# LPC1114_--_Valdez_Mutant_v_02.net
KiCad netlist of a schematic drawn in EAGLE
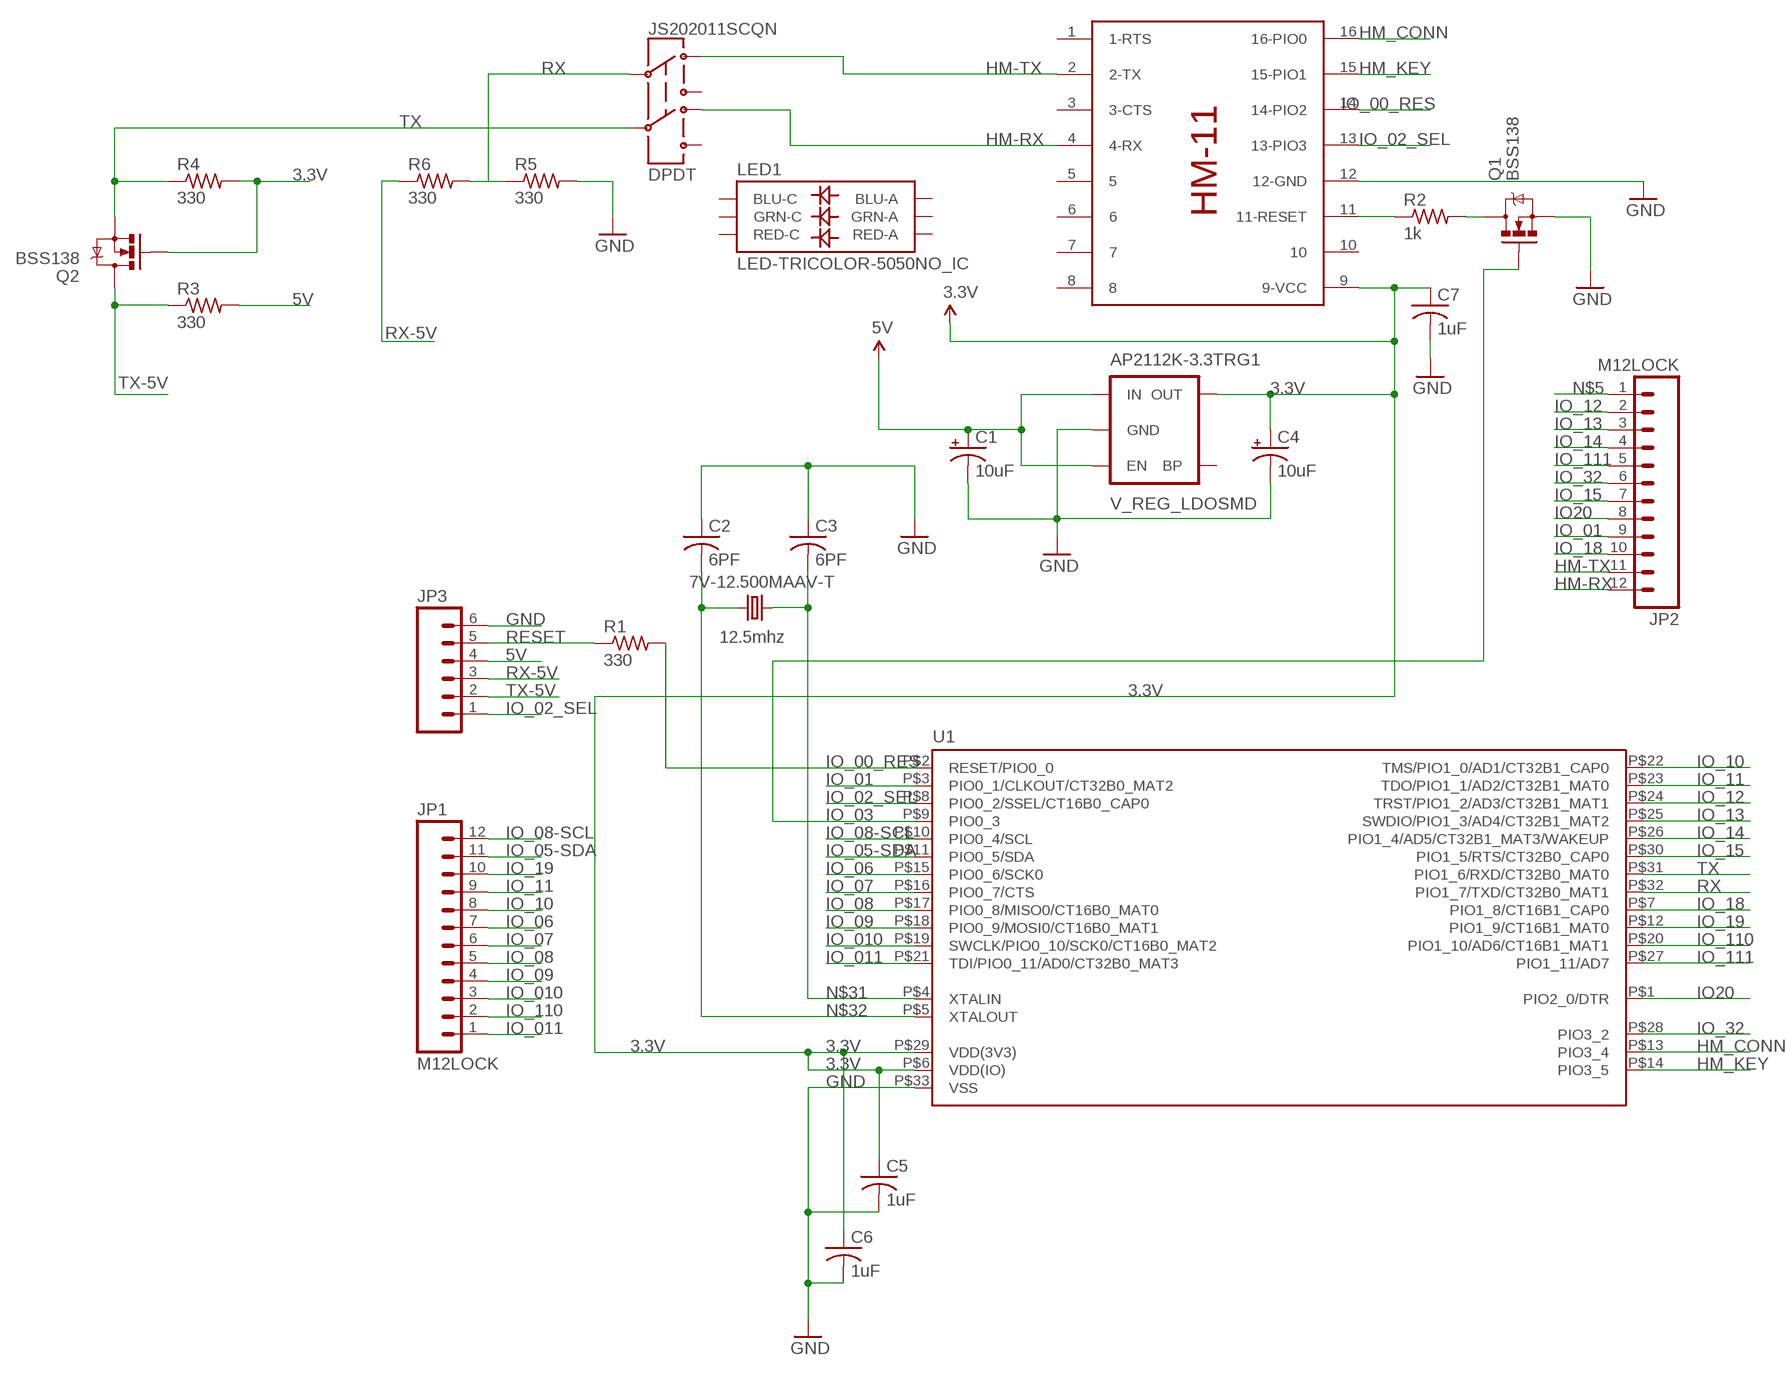
[diagram p0: schematic, sheet 1]

(export (version "E")
  (design (tool "Eeschema 10.0.6"))
  (components
    (comp (ref "7V-12.500MAAV-T")
      (value "12.5mhz")
      (footprint "eagle-import:CRYSTAL-SMD-5X3")
      (libsource (lib "eagle-import") (part "CRYSTAL5X3"))
    )
    (comp (ref "AP2112K-3.3TRG1")
      (value "V_REG_LDOSMD")
      (footprint "eagle-import:SOT23-5")
      (libsource (lib "eagle-import") (part "V_REG_LDOSMD"))
    )
    (comp (ref "C1")
      (value "10uF")
      (footprint "eagle-import:EIA3216")
      (libsource (lib "eagle-import") (part "CAP_POL1206"))
    )
    (comp (ref "C2")
      (value "6PF")
      (footprint "eagle-import:C0402K")
      (libsource (lib "eagle-import") (part "C-USC0402K"))
    )
    (comp (ref "C3")
      (value "6PF")
      (footprint "eagle-import:C0402K")
      (libsource (lib "eagle-import") (part "C-USC0402K"))
    )
    (comp (ref "C4")
      (value "10uF")
      (footprint "eagle-import:EIA3216")
      (libsource (lib "eagle-import") (part "CAP_POL1206"))
    )
    (comp (ref "C5")
      (value "1uF")
      (footprint "eagle-import:C0402K")
      (libsource (lib "eagle-import") (part "C-USC0402K"))
    )
    (comp (ref "C6")
      (value "1uF")
      (footprint "eagle-import:C0402K")
      (libsource (lib "eagle-import") (part "C-USC0402K"))
    )
    (comp (ref "C7")
      (value "1uF")
      (footprint "eagle-import:C0402K")
      (libsource (lib "eagle-import") (part "C-USC0402K"))
    )
    (comp (ref "JP1")
      (value "M12LOCK")
      (footprint "eagle-import:1X12_LOCK")
      (libsource (lib "eagle-import") (part "M12LOCK"))
    )
    (comp (ref "JP2")
      (value "M12LOCK")
      (footprint "eagle-import:1X12_LOCK")
      (libsource (lib "eagle-import") (part "M12LOCK"))
    )
    (comp (ref "JP3")
      (value "M06LOCK")
      (footprint "eagle-import:1X06_LOCK")
      (libsource (lib "eagle-import") (part "M06LOCK"))
    )
    (comp (ref "JS202011SCQN")
      (value "DPDT")
      (footprint "eagle-import:AYZ0202")
      (libsource (lib "eagle-import") (part "SWITCH-DPDTAYZ0202"))
    )
    (comp (ref "LED1")
      (value "LED-TRICOLOR-5050NO_IC")
      (footprint "eagle-import:LED-TRICOLOR-5050")
      (libsource (lib "eagle-import") (part "LED-TRICOLOR-5050NO_IC"))
    )
    (comp (ref "Q1")
      (value "BSS138")
      (footprint "eagle-import:SOT23")
      (libsource (lib "eagle-import") (part "MOSFET-NCHANNELBSS138"))
    )
    (comp (ref "Q2")
      (value "BSS138")
      (footprint "eagle-import:SOT23")
      (libsource (lib "eagle-import") (part "MOSFET-NCHANNELBSS138"))
    )
    (comp (ref "R1")
      (value "330")
      (footprint "eagle-import:R0402")
      (libsource (lib "eagle-import") (part "R-US_R0402"))
    )
    (comp (ref "R2")
      (value "1k")
      (footprint "eagle-import:R0402")
      (libsource (lib "eagle-import") (part "R-US_R0402"))
    )
    (comp (ref "R3")
      (value "330")
      (footprint "eagle-import:R0402")
      (libsource (lib "eagle-import") (part "R-US_R0402"))
    )
    (comp (ref "R4")
      (value "330")
      (footprint "eagle-import:R0402")
      (libsource (lib "eagle-import") (part "R-US_R0402"))
    )
    (comp (ref "R5")
      (value "330")
      (footprint "eagle-import:R0402")
      (libsource (lib "eagle-import") (part "R-US_R0402"))
    )
    (comp (ref "R6")
      (value "330")
      (footprint "eagle-import:R0402")
      (libsource (lib "eagle-import") (part "R-US_R0402"))
    )
    (comp (ref "U$1")
      (value "HM-11")
      (footprint "eagle-import:HM-11")
      (libsource (lib "eagle-import") (part "HM-11"))
    )
    (comp (ref "U1")
      (value "LPC1113/4_QFN")
      (footprint "eagle-import:HVQFN33-7X7")
      (fields (field (name "MANF") "NXP"))
      (libsource (lib "eagle-import") (part "LPC1113/4_QFN"))
    )
  )
  (nets
    (net (code "1") (name "/HM-RX") (class "Default")
      (node (ref "JP2") (pin "12") (pinfunction "12_12") (pintype "passive"))
      (node (ref "JS202011SCQN") (pin "4") (pinfunction "4_4") (pintype "bidirectional"))
      (node (ref "U$1") (pin "4") (pinfunction "4-RX_4") (pintype "bidirectional"))
    )
    (net (code "2") (name "/HM-TX") (class "Default")
      (node (ref "JP2") (pin "11") (pinfunction "11_11") (pintype "passive"))
      (node (ref "JS202011SCQN") (pin "1") (pinfunction "1_1") (pintype "bidirectional"))
      (node (ref "U$1") (pin "2") (pinfunction "2-TX_2") (pintype "bidirectional"))
    )
    (net (code "3") (name "/HM_CONN") (class "Default")
      (node (ref "U$1") (pin "16") (pinfunction "16-PIO0_16") (pintype "bidirectional"))
      (node (ref "U1") (pin "P$13") (pinfunction "PIO3_4_P$13") (pintype "bidirectional"))
    )
    (net (code "4") (name "/HM_KEY") (class "Default")
      (node (ref "U$1") (pin "15") (pinfunction "15-PIO1_15") (pintype "bidirectional"))
      (node (ref "U1") (pin "P$14") (pinfunction "PIO3_5_P$14") (pintype "bidirectional"))
    )
    (net (code "5") (name "/IO20") (class "Default")
      (node (ref "JP2") (pin "8") (pinfunction "8_8") (pintype "passive"))
      (node (ref "U1") (pin "P$1") (pinfunction "PIO2_0/DTR_P$1") (pintype "bidirectional"))
    )
    (net (code "6") (name "/IO_00_RES") (class "Default")
      (node (ref "R1") (pin "2") (pinfunction "2_2") (pintype "passive"))
      (node (ref "U$1") (pin "14") (pinfunction "14-PIO2_14") (pintype "bidirectional"))
      (node (ref "U1") (pin "P$2") (pinfunction "RESET/PIO0_0_P$2") (pintype "bidirectional"))
    )
    (net (code "7") (name "/IO_01") (class "Default")
      (node (ref "JP2") (pin "9") (pinfunction "9_9") (pintype "passive"))
      (node (ref "U1") (pin "P$3") (pinfunction "PIO0_1/CLKOUT/CT32B0_MAT2_P$3") (pintype "bidirectional"))
    )
    (net (code "8") (name "/IO_02_SEL") (class "Default")
      (node (ref "JP3") (pin "1") (pinfunction "1_1") (pintype "passive"))
      (node (ref "U$1") (pin "13") (pinfunction "13-PIO3_13") (pintype "bidirectional"))
      (node (ref "U1") (pin "P$8") (pinfunction "PIO0_2/SSEL/CT16B0_CAP0_P$8") (pintype "bidirectional"))
    )
    (net (code "9") (name "/IO_03") (class "Default")
      (node (ref "Q1") (pin "1") (pinfunction "G_1") (pintype "passive"))
      (node (ref "U1") (pin "P$9") (pinfunction "PIO0_3_P$9") (pintype "bidirectional"))
    )
    (net (code "10") (name "/IO_05-SDA") (class "Default")
      (node (ref "JP1") (pin "11") (pinfunction "11_11") (pintype "passive"))
      (node (ref "U1") (pin "P$11") (pinfunction "PIO0_5/SDA_P$11") (pintype "bidirectional"))
    )
    (net (code "11") (name "/IO_06") (class "Default")
      (node (ref "JP1") (pin "7") (pinfunction "7_7") (pintype "passive"))
      (node (ref "U1") (pin "P$15") (pinfunction "PIO0_6/SCK0_P$15") (pintype "bidirectional"))
    )
    (net (code "12") (name "/IO_07") (class "Default")
      (node (ref "JP1") (pin "6") (pinfunction "6_6") (pintype "passive"))
      (node (ref "U1") (pin "P$16") (pinfunction "PIO0_7/CTS_P$16") (pintype "bidirectional"))
    )
    (net (code "13") (name "/IO_08") (class "Default")
      (node (ref "JP1") (pin "5") (pinfunction "5_5") (pintype "passive"))
      (node (ref "U1") (pin "P$17") (pinfunction "PIO0_8/MISO0/CT16B0_MAT0_P$17") (pintype "bidirectional"))
    )
    (net (code "14") (name "/IO_08-SCL") (class "Default")
      (node (ref "JP1") (pin "12") (pinfunction "12_12") (pintype "passive"))
      (node (ref "U1") (pin "P$10") (pinfunction "PIO0_4/SCL_P$10") (pintype "bidirectional"))
    )
    (net (code "15") (name "/IO_09") (class "Default")
      (node (ref "JP1") (pin "4") (pinfunction "4_4") (pintype "passive"))
      (node (ref "U1") (pin "P$18") (pinfunction "PIO0_9/MOSI0/CT16B0_MAT1_P$18") (pintype "bidirectional"))
    )
    (net (code "16") (name "/IO_10") (class "Default")
      (node (ref "JP1") (pin "8") (pinfunction "8_8") (pintype "passive"))
      (node (ref "U1") (pin "P$22") (pinfunction "TMS/PIO1_0/AD1/CT32B1_CAP0_P$22") (pintype "bidirectional"))
    )
    (net (code "17") (name "/IO_010") (class "Default")
      (node (ref "JP1") (pin "3") (pinfunction "3_3") (pintype "passive"))
      (node (ref "U1") (pin "P$19") (pinfunction "SWCLK/PIO0_10/SCK0/CT16B0_MAT2_P$19") (pintype "bidirectional"))
    )
    (net (code "18") (name "/IO_011") (class "Default")
      (node (ref "JP1") (pin "1") (pinfunction "1_1") (pintype "passive"))
      (node (ref "U1") (pin "P$21") (pinfunction "TDI/PIO0_11/AD0/CT32B0_MAT3_P$21") (pintype "bidirectional"))
    )
    (net (code "19") (name "/IO_11") (class "Default")
      (node (ref "JP1") (pin "9") (pinfunction "9_9") (pintype "passive"))
      (node (ref "U1") (pin "P$23") (pinfunction "TDO/PIO1_1/AD2/CT32B1_MAT0_P$23") (pintype "bidirectional"))
    )
    (net (code "20") (name "/IO_12") (class "Default")
      (node (ref "JP2") (pin "2") (pinfunction "2_2") (pintype "passive"))
      (node (ref "U1") (pin "P$24") (pinfunction "TRST/PIO1_2/AD3/CT32B1_MAT1_P$24") (pintype "bidirectional"))
    )
    (net (code "21") (name "/IO_13") (class "Default")
      (node (ref "JP2") (pin "3") (pinfunction "3_3") (pintype "passive"))
      (node (ref "U1") (pin "P$25") (pinfunction "SWDIO/PIO1_3/AD4/CT32B1_MAT2_P$25") (pintype "bidirectional"))
    )
    (net (code "22") (name "/IO_14") (class "Default")
      (node (ref "JP2") (pin "4") (pinfunction "4_4") (pintype "passive"))
      (node (ref "U1") (pin "P$26") (pinfunction "PIO1_4/AD5/CT32B1_MAT3/WAKEUP_P$26") (pintype "bidirectional"))
    )
    (net (code "23") (name "/IO_15") (class "Default")
      (node (ref "JP2") (pin "7") (pinfunction "7_7") (pintype "passive"))
      (node (ref "U1") (pin "P$30") (pinfunction "PIO1_5/RTS/CT32B0_CAP0_P$30") (pintype "bidirectional"))
    )
    (net (code "24") (name "/IO_18") (class "Default")
      (node (ref "JP2") (pin "10") (pinfunction "10_10") (pintype "passive"))
      (node (ref "U1") (pin "P$7") (pinfunction "PIO1_8/CT16B1_CAP0_P$7") (pintype "bidirectional"))
    )
    (net (code "25") (name "/IO_19") (class "Default")
      (node (ref "JP1") (pin "10") (pinfunction "10_10") (pintype "passive"))
      (node (ref "U1") (pin "P$12") (pinfunction "PIO1_9/CT16B1_MAT0_P$12") (pintype "bidirectional"))
    )
    (net (code "26") (name "/IO_32") (class "Default")
      (node (ref "JP2") (pin "6") (pinfunction "6_6") (pintype "passive"))
      (node (ref "U1") (pin "P$28") (pinfunction "PIO3_2_P$28") (pintype "bidirectional"))
    )
    (net (code "27") (name "/IO_110") (class "Default")
      (node (ref "JP1") (pin "2") (pinfunction "2_2") (pintype "passive"))
      (node (ref "U1") (pin "P$20") (pinfunction "PIO1_10/AD6/CT16B1_MAT1_P$20") (pintype "bidirectional"))
    )
    (net (code "28") (name "/IO_111") (class "Default")
      (node (ref "JP2") (pin "5") (pinfunction "5_5") (pintype "passive"))
      (node (ref "U1") (pin "P$27") (pinfunction "PIO1_11/AD7_P$27") (pintype "bidirectional"))
    )
    (net (code "29") (name "/N$5") (class "Default")
      (node (ref "JP2") (pin "1") (pinfunction "1_1") (pintype "passive"))
    )
    (net (code "30") (name "/N$31") (class "Default")
      (node (ref "7V-12.500MAAV-T") (pin "3") (pinfunction "2_3") (pintype "passive"))
      (node (ref "C3") (pin "2") (pinfunction "2_2") (pintype "passive"))
      (node (ref "U1") (pin "P$4") (pinfunction "XTALIN_P$4") (pintype "input"))
    )
    (net (code "31") (name "/N$32") (class "Default")
      (node (ref "7V-12.500MAAV-T") (pin "1") (pinfunction "1_1") (pintype "passive"))
      (node (ref "C2") (pin "2") (pinfunction "2_2") (pintype "passive"))
      (node (ref "U1") (pin "P$5") (pinfunction "XTALOUT_P$5") (pintype "output"))
    )
    (net (code "32") (name "/RESET") (class "Default")
      (node (ref "JP3") (pin "5") (pinfunction "5_5") (pintype "passive"))
      (node (ref "R1") (pin "1") (pinfunction "1_1") (pintype "passive"))
    )
    (net (code "33") (name "/RX") (class "Default")
      (node (ref "JS202011SCQN") (pin "2") (pinfunction "2_2") (pintype "bidirectional"))
      (node (ref "R5") (pin "1") (pinfunction "1_1") (pintype "passive"))
      (node (ref "R6") (pin "2") (pinfunction "2_2") (pintype "passive"))
      (node (ref "U1") (pin "P$32") (pinfunction "PIO1_7/TXD/CT32B0_MAT1_P$32") (pintype "bidirectional"))
    )
    (net (code "34") (name "/RX-5V") (class "Default")
      (node (ref "JP3") (pin "3") (pinfunction "3_3") (pintype "passive"))
      (node (ref "R6") (pin "1") (pinfunction "1_1") (pintype "passive"))
    )
    (net (code "35") (name "/TX") (class "Default")
      (node (ref "JS202011SCQN") (pin "5") (pinfunction "5_5") (pintype "bidirectional"))
      (node (ref "Q2") (pin "2") (pinfunction "S_2") (pintype "passive"))
      (node (ref "R4") (pin "1") (pinfunction "1_1") (pintype "passive"))
      (node (ref "U1") (pin "P$31") (pinfunction "PIO1_6/RXD/CT32B0_MAT0_P$31") (pintype "bidirectional"))
    )
    (net (code "36") (name "/TX-5V") (class "Default")
      (node (ref "JP3") (pin "2") (pinfunction "2_2") (pintype "passive"))
      (node (ref "Q2") (pin "3") (pinfunction "D_3") (pintype "passive"))
      (node (ref "R3") (pin "1") (pinfunction "1_1") (pintype "passive"))
    )
    (net (code "37") (name "3.3V") (class "Default")
      (node (ref "AP2112K-3.3TRG1") (pin "5") (pinfunction "OUT_5") (pintype "passive"))
      (node (ref "C4") (pin "A") (pinfunction "+_A") (pintype "passive"))
      (node (ref "C5") (pin "1") (pinfunction "1_1") (pintype "passive"))
      (node (ref "C6") (pin "1") (pinfunction "1_1") (pintype "passive"))
      (node (ref "C7") (pin "1") (pinfunction "1_1") (pintype "passive"))
      (node (ref "Q2") (pin "1") (pinfunction "G_1") (pintype "passive"))
      (node (ref "R4") (pin "2") (pinfunction "2_2") (pintype "passive"))
      (node (ref "U$1") (pin "9") (pinfunction "9-VCC_9") (pintype "bidirectional"))
      (node (ref "U1") (pin "P$29") (pinfunction "VDD(3V3)_P$29") (pintype "power_in"))
      (node (ref "U1") (pin "P$6") (pinfunction "VDD(IO)_P$6") (pintype "power_in"))
    )
    (net (code "38") (name "5V") (class "Default")
      (node (ref "AP2112K-3.3TRG1") (pin "1") (pinfunction "IN_1") (pintype "input"))
      (node (ref "AP2112K-3.3TRG1") (pin "3") (pinfunction "EN_3") (pintype "input"))
      (node (ref "C1") (pin "A") (pinfunction "+_A") (pintype "passive"))
      (node (ref "JP3") (pin "4") (pinfunction "4_4") (pintype "passive"))
      (node (ref "R3") (pin "2") (pinfunction "2_2") (pintype "passive"))
    )
    (net (code "39") (name "GND") (class "Default")
      (node (ref "AP2112K-3.3TRG1") (pin "2") (pinfunction "GND_2") (pintype "input"))
      (node (ref "C1") (pin "C") (pinfunction "-_C") (pintype "passive"))
      (node (ref "C2") (pin "1") (pinfunction "1_1") (pintype "passive"))
      (node (ref "C3") (pin "1") (pinfunction "1_1") (pintype "passive"))
      (node (ref "C4") (pin "C") (pinfunction "-_C") (pintype "passive"))
      (node (ref "C5") (pin "2") (pinfunction "2_2") (pintype "passive"))
      (node (ref "C6") (pin "2") (pinfunction "2_2") (pintype "passive"))
      (node (ref "C7") (pin "2") (pinfunction "2_2") (pintype "passive"))
      (node (ref "JP3") (pin "6") (pinfunction "6_6") (pintype "passive"))
      (node (ref "Q1") (pin "2") (pinfunction "S_2") (pintype "passive"))
      (node (ref "R5") (pin "2") (pinfunction "2_2") (pintype "passive"))
      (node (ref "U$1") (pin "12") (pinfunction "12-GND_12") (pintype "bidirectional"))
      (node (ref "U1") (pin "P$33") (pinfunction "VSS_P$33") (pintype "power_in"))
    )
    (net (code "40") (name "Net-(Q1-D)") (class "Default")
      (node (ref "Q1") (pin "3") (pinfunction "D_3") (pintype "passive"))
      (node (ref "R2") (pin "2") (pinfunction "2_2") (pintype "passive"))
    )
    (net (code "41") (name "Net-(U$1-11-RESET)") (class "Default")
      (node (ref "R2") (pin "1") (pinfunction "1_1") (pintype "passive"))
      (node (ref "U$1") (pin "11") (pinfunction "11-RESET_11") (pintype "bidirectional"))
    )
    (net (code "42") (name "unconnected-(AP2112K-3.3TRG1-BP-Pad4)") (class "Default")
      (node (ref "AP2112K-3.3TRG1") (pin "4") (pinfunction "BP_4") (pintype "input"))
    )
    (net (code "43") (name "unconnected-(JS202011SCQN-Pad3)") (class "Default")
      (node (ref "JS202011SCQN") (pin "3") (pinfunction "3_3") (pintype "bidirectional"))
    )
    (net (code "44") (name "unconnected-(JS202011SCQN-Pad6)") (class "Default")
      (node (ref "JS202011SCQN") (pin "6") (pinfunction "6_6") (pintype "bidirectional"))
    )
    (net (code "45") (name "unconnected-(LED1-BLU-A-Pad3)") (class "Default")
      (node (ref "LED1") (pin "3") (pinfunction "BLU-A_3") (pintype "bidirectional"))
    )
    (net (code "46") (name "unconnected-(LED1-BLU-C-Pad4)") (class "Default")
      (node (ref "LED1") (pin "4") (pinfunction "BLU-C_4") (pintype "bidirectional"))
    )
    (net (code "47") (name "unconnected-(LED1-GRN-A-Pad1)") (class "Default")
      (node (ref "LED1") (pin "1") (pinfunction "GRN-A_1") (pintype "bidirectional"))
    )
    (net (code "48") (name "unconnected-(LED1-GRN-C-Pad6)") (class "Default")
      (node (ref "LED1") (pin "6") (pinfunction "GRN-C_6") (pintype "bidirectional"))
    )
    (net (code "49") (name "unconnected-(LED1-RED-A-Pad2)") (class "Default")
      (node (ref "LED1") (pin "2") (pinfunction "RED-A_2") (pintype "bidirectional"))
    )
    (net (code "50") (name "unconnected-(LED1-RED-C-Pad5)") (class "Default")
      (node (ref "LED1") (pin "5") (pinfunction "RED-C_5") (pintype "bidirectional"))
    )
    (net (code "51") (name "unconnected-(U$1-1-RTS-Pad1)") (class "Default")
      (node (ref "U$1") (pin "1") (pinfunction "1-RTS_1") (pintype "bidirectional"))
    )
    (net (code "52") (name "unconnected-(U$1-3-CTS-Pad3)") (class "Default")
      (node (ref "U$1") (pin "3") (pinfunction "3-CTS_3") (pintype "bidirectional"))
    )
    (net (code "53") (name "unconnected-(U$1-Pad5)") (class "Default")
      (node (ref "U$1") (pin "5") (pinfunction "5_5") (pintype "bidirectional"))
    )
    (net (code "54") (name "unconnected-(U$1-Pad6)") (class "Default")
      (node (ref "U$1") (pin "6") (pinfunction "6_6") (pintype "bidirectional"))
    )
    (net (code "55") (name "unconnected-(U$1-Pad7)") (class "Default")
      (node (ref "U$1") (pin "7") (pinfunction "7_7") (pintype "bidirectional"))
    )
    (net (code "56") (name "unconnected-(U$1-Pad8)") (class "Default")
      (node (ref "U$1") (pin "8") (pinfunction "8_8") (pintype "bidirectional"))
    )
    (net (code "57") (name "unconnected-(U$1-Pad10)") (class "Default")
      (node (ref "U$1") (pin "10") (pinfunction "10_10") (pintype "bidirectional"))
    )
  )
)
